# MCU.net
KiCad netlist of a schematic drawn in Altium Designer
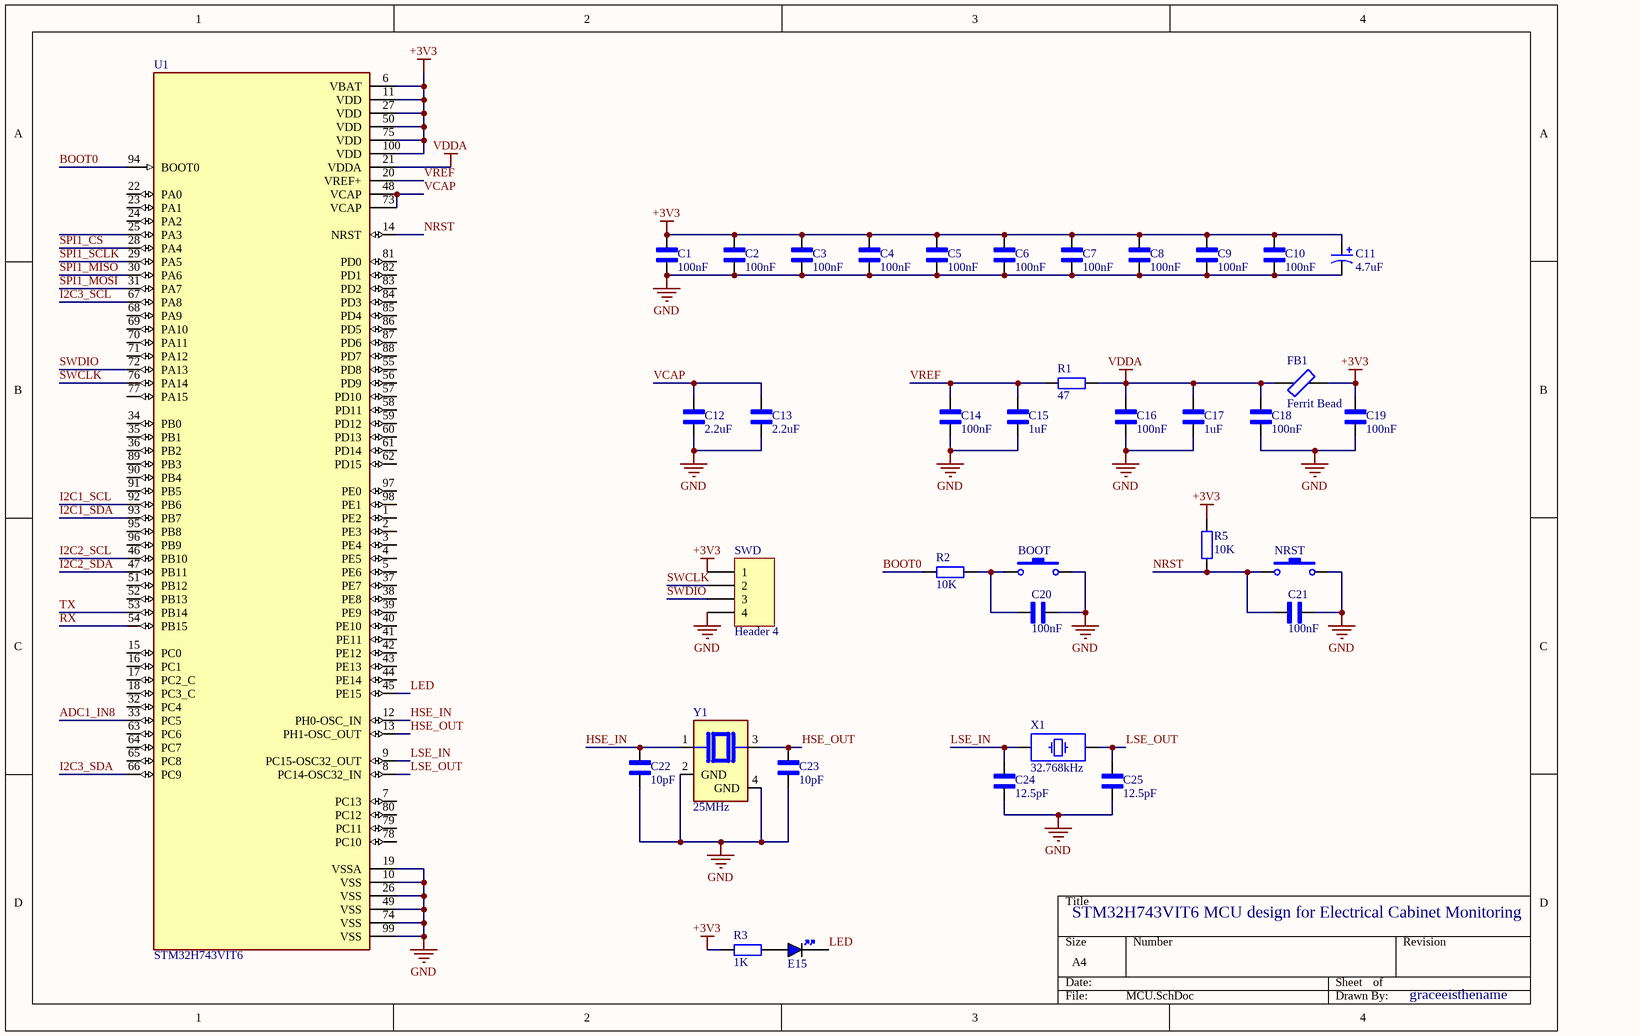
[diagram p0: MCU.SchDoc]

(export (version "E")
  (design (tool "Eeschema 10.0.6"))
  (components
    (comp (ref "BOOT")
      (value "SW-SMD")
      (footprint "SW-SMD")
      (description "Switch")
      (fields (field (name "PUBLISHER") "Altium Limited"))
      (libsource (lib "My Library") (part "SW-SMD"))
    )
    (comp (ref "C1")
      (value "100nF")
      (footprint "CAPC2012X145N")
      (description "39 pF Â±2% 200V Ceramic Capacitor C0G, NP0 0805 (2012 Metric)")
      (fields (field (name "MF") "Vishay Vitramon") (field (name "MP") "VJ0805A390GXCAP"))
      (libsource (lib "VJ0805A390GXCAP") (part "VJ0805A390GXCAP"))
    )
    (comp (ref "C2")
      (value "100nF")
      (footprint "CAPC2012X145N")
      (description "39 pF Â±2% 200V Ceramic Capacitor C0G, NP0 0805 (2012 Metric)")
      (fields (field (name "MF") "Vishay Vitramon") (field (name "MP") "VJ0805A390GXCAP"))
      (libsource (lib "VJ0805A390GXCAP") (part "VJ0805A390GXCAP"))
    )
    (comp (ref "C3")
      (value "100nF")
      (footprint "CAPC2012X145N")
      (description "39 pF Â±2% 200V Ceramic Capacitor C0G, NP0 0805 (2012 Metric)")
      (fields (field (name "MF") "Vishay Vitramon") (field (name "MP") "VJ0805A390GXCAP"))
      (libsource (lib "VJ0805A390GXCAP") (part "VJ0805A390GXCAP"))
    )
    (comp (ref "C4")
      (value "100nF")
      (footprint "CAPC2012X145N")
      (description "39 pF Â±2% 200V Ceramic Capacitor C0G, NP0 0805 (2012 Metric)")
      (fields (field (name "MF") "Vishay Vitramon") (field (name "MP") "VJ0805A390GXCAP"))
      (libsource (lib "VJ0805A390GXCAP") (part "VJ0805A390GXCAP"))
    )
    (comp (ref "C5")
      (value "100nF")
      (footprint "CAPC2012X145N")
      (description "39 pF Â±2% 200V Ceramic Capacitor C0G, NP0 0805 (2012 Metric)")
      (fields (field (name "MF") "Vishay Vitramon") (field (name "MP") "VJ0805A390GXCAP"))
      (libsource (lib "VJ0805A390GXCAP") (part "VJ0805A390GXCAP"))
    )
    (comp (ref "C6")
      (value "100nF")
      (footprint "CAPC2012X145N")
      (description "39 pF Â±2% 200V Ceramic Capacitor C0G, NP0 0805 (2012 Metric)")
      (fields (field (name "MF") "Vishay Vitramon") (field (name "MP") "VJ0805A390GXCAP"))
      (libsource (lib "VJ0805A390GXCAP") (part "VJ0805A390GXCAP"))
    )
    (comp (ref "C7")
      (value "100nF")
      (footprint "CAPC2012X145N")
      (description "39 pF Â±2% 200V Ceramic Capacitor C0G, NP0 0805 (2012 Metric)")
      (fields (field (name "MF") "Vishay Vitramon") (field (name "MP") "VJ0805A390GXCAP"))
      (libsource (lib "VJ0805A390GXCAP") (part "VJ0805A390GXCAP"))
    )
    (comp (ref "C8")
      (value "100nF")
      (footprint "CAPC2012X145N")
      (description "39 pF Â±2% 200V Ceramic Capacitor C0G, NP0 0805 (2012 Metric)")
      (fields (field (name "MF") "Vishay Vitramon") (field (name "MP") "VJ0805A390GXCAP"))
      (libsource (lib "VJ0805A390GXCAP") (part "VJ0805A390GXCAP"))
    )
    (comp (ref "C9")
      (value "100nF")
      (footprint "CAPC2012X145N")
      (description "39 pF Â±2% 200V Ceramic Capacitor C0G, NP0 0805 (2012 Metric)")
      (fields (field (name "MF") "Vishay Vitramon") (field (name "MP") "VJ0805A390GXCAP"))
      (libsource (lib "VJ0805A390GXCAP") (part "VJ0805A390GXCAP"))
    )
    (comp (ref "C10")
      (value "100nF")
      (footprint "CAPC2012X145N")
      (description "39 pF Â±2% 200V Ceramic Capacitor C0G, NP0 0805 (2012 Metric)")
      (fields (field (name "MF") "Vishay Vitramon") (field (name "MP") "VJ0805A390GXCAP"))
      (libsource (lib "VJ0805A390GXCAP") (part "VJ0805A390GXCAP"))
    )
    (comp (ref "C11")
      (value "4.7uF")
      (footprint "CAPC2012X145N")
      (description "Polazied Tantalum Capacitor")
      (libsource (lib "My Library") (part "CAP_TAN_SMD"))
    )
    (comp (ref "C12")
      (value "2.2uF")
      (footprint "CAPC2012X145N")
      (description "39 pF Â±2% 200V Ceramic Capacitor C0G, NP0 0805 (2012 Metric)")
      (fields (field (name "MF") "Vishay Vitramon") (field (name "MP") "VJ0805A390GXCAP"))
      (libsource (lib "VJ0805A390GXCAP") (part "VJ0805A390GXCAP"))
    )
    (comp (ref "C13")
      (value "2.2uF")
      (footprint "CAPC2012X145N")
      (description "39 pF Â±2% 200V Ceramic Capacitor C0G, NP0 0805 (2012 Metric)")
      (fields (field (name "MF") "Vishay Vitramon") (field (name "MP") "VJ0805A390GXCAP"))
      (libsource (lib "VJ0805A390GXCAP") (part "VJ0805A390GXCAP"))
    )
    (comp (ref "C14")
      (value "100nF")
      (footprint "CAPC2012X145N")
      (description "39 pF Â±2% 200V Ceramic Capacitor C0G, NP0 0805 (2012 Metric)")
      (fields (field (name "MF") "Vishay Vitramon") (field (name "MP") "VJ0805A390GXCAP"))
      (libsource (lib "VJ0805A390GXCAP") (part "VJ0805A390GXCAP"))
    )
    (comp (ref "C15")
      (value "1uF")
      (footprint "CAPC2012X145N")
      (description "39 pF Â±2% 200V Ceramic Capacitor C0G, NP0 0805 (2012 Metric)")
      (fields (field (name "MF") "Vishay Vitramon") (field (name "MP") "VJ0805A390GXCAP"))
      (libsource (lib "VJ0805A390GXCAP") (part "VJ0805A390GXCAP"))
    )
    (comp (ref "C16")
      (value "100nF")
      (footprint "CAPC2012X145N")
      (description "39 pF Â±2% 200V Ceramic Capacitor C0G, NP0 0805 (2012 Metric)")
      (fields (field (name "MF") "Vishay Vitramon") (field (name "MP") "VJ0805A390GXCAP"))
      (libsource (lib "VJ0805A390GXCAP") (part "VJ0805A390GXCAP"))
    )
    (comp (ref "C17")
      (value "1uF")
      (footprint "CAPC2012X145N")
      (description "39 pF Â±2% 200V Ceramic Capacitor C0G, NP0 0805 (2012 Metric)")
      (fields (field (name "MF") "Vishay Vitramon") (field (name "MP") "VJ0805A390GXCAP"))
      (libsource (lib "VJ0805A390GXCAP") (part "VJ0805A390GXCAP"))
    )
    (comp (ref "C18")
      (value "100nF")
      (footprint "CAPC2012X145N")
      (description "39 pF Â±2% 200V Ceramic Capacitor C0G, NP0 0805 (2012 Metric)")
      (fields (field (name "MF") "Vishay Vitramon") (field (name "MP") "VJ0805A390GXCAP"))
      (libsource (lib "VJ0805A390GXCAP") (part "VJ0805A390GXCAP"))
    )
    (comp (ref "C19")
      (value "100nF")
      (footprint "CAPC2012X145N")
      (description "39 pF Â±2% 200V Ceramic Capacitor C0G, NP0 0805 (2012 Metric)")
      (fields (field (name "MF") "Vishay Vitramon") (field (name "MP") "VJ0805A390GXCAP"))
      (libsource (lib "VJ0805A390GXCAP") (part "VJ0805A390GXCAP"))
    )
    (comp (ref "C20")
      (value "100nF")
      (footprint "CAPC2012X145N")
      (description "39 pF Â±2% 200V Ceramic Capacitor C0G, NP0 0805 (2012 Metric)")
      (fields (field (name "MF") "Vishay Vitramon") (field (name "MP") "VJ0805A390GXCAP"))
      (libsource (lib "") (part "VJ0805A390GXCAP_1"))
    )
    (comp (ref "C21")
      (value "100nF")
      (footprint "CAPC2012X145N")
      (description "39 pF Â±2% 200V Ceramic Capacitor C0G, NP0 0805 (2012 Metric)")
      (fields (field (name "MF") "Vishay Vitramon") (field (name "MP") "VJ0805A390GXCAP"))
      (libsource (lib "") (part "VJ0805A390GXCAP_1"))
    )
    (comp (ref "C22")
      (value "10pF")
      (footprint "CAPC2012X145N")
      (description "39 pF Â±2% 200V Ceramic Capacitor C0G, NP0 0805 (2012 Metric)")
      (fields (field (name "MF") "Vishay Vitramon") (field (name "MP") "VJ0805A390GXCAP"))
      (libsource (lib "VJ0805A390GXCAP") (part "VJ0805A390GXCAP"))
    )
    (comp (ref "C23")
      (value "10pF")
      (footprint "CAPC2012X145N")
      (description "39 pF Â±2% 200V Ceramic Capacitor C0G, NP0 0805 (2012 Metric)")
      (fields (field (name "MF") "Vishay Vitramon") (field (name "MP") "VJ0805A390GXCAP"))
      (libsource (lib "VJ0805A390GXCAP") (part "VJ0805A390GXCAP"))
    )
    (comp (ref "C24")
      (value "12.5pF")
      (footprint "CAPC2012X145N")
      (description "39 pF Â±2% 200V Ceramic Capacitor C0G, NP0 0805 (2012 Metric)")
      (fields (field (name "MF") "Vishay Vitramon") (field (name "MP") "VJ0805A390GXCAP"))
      (libsource (lib "VJ0805A390GXCAP") (part "VJ0805A390GXCAP"))
    )
    (comp (ref "C25")
      (value "12.5pF")
      (footprint "CAPC2012X145N")
      (description "39 pF Â±2% 200V Ceramic Capacitor C0G, NP0 0805 (2012 Metric)")
      (fields (field (name "MF") "Vishay Vitramon") (field (name "MP") "VJ0805A390GXCAP"))
      (libsource (lib "VJ0805A390GXCAP") (part "VJ0805A390GXCAP"))
    )
    (comp (ref "E15")
      (value "BLUE")
      (footprint "LED_0805_BLUE")
      (description "LED 0805 BLUE SMD")
      (libsource (lib "Schematic-Lib-PhilsLab") (part "LED_0805_BLUE"))
    )
    (comp (ref "FB1")
      (value "Ferrit Bead")
      (footprint "RES-SMD-0805")
      (description "Generic Ferrit Bead")
      (libsource (lib "My Library") (part "Ferrit Bead"))
    )
    (comp (ref "NRST")
      (value "SW-SMD")
      (footprint "SW-SMD")
      (description "Switch")
      (fields (field (name "PUBLISHER") "Altium Limited"))
      (libsource (lib "My Library") (part "SW-SMD"))
    )
    (comp (ref "R1")
      (value "47")
      (footprint "SM-0805")
      (description "Resistor SMD")
      (libsource (lib "My Library") (part "RM"))
    )
    (comp (ref "R2")
      (value "10K")
      (footprint "SM-0805")
      (description "Resistor SMD")
      (libsource (lib "My Library") (part "RM"))
    )
    (comp (ref "R3")
      (value "1K")
      (footprint "SM-0805")
      (description "Resistor SMD")
      (libsource (lib "My Library") (part "RM"))
    )
    (comp (ref "R5")
      (value "10K")
      (footprint "SM-0805")
      (description "Resistor SMD")
      (libsource (lib "My Library") (part "RM"))
    )
    (comp (ref "SWD")
      (value "Header 4")
      (footprint "HDR1X4")
      (description "Header, 4-Pin")
      (fields (field (name "PUBLISHER") "Altium Limited"))
      (libsource (lib "My Library") (part "Header 4"))
    )
    (comp (ref "U1")
      (value "STM32H743VIT6")
      (footprint "QFP50P1600X1600X160-100N")
      (fields (field (name "MF") "STMicroelectronics"))
      (libsource (lib "STM32H743VIT6") (part "STM32H743VIT6"))
    )
    (comp (ref "X1")
      (value "32.768kHz")
      (footprint "XTAL_3215-2")
      (description "Crystal SMD 3215")
      (libsource (lib "Schematic-Lib-PhilsLab") (part "XTAL_3215"))
    )
    (comp (ref "Y1")
      (value "25MHz")
      (footprint "XTAL_ABM8G-25.000MHZ-B4Y-T")
      (description "25 MHz Â±30ppm Crystal 10pF 60 Ohms 4-SMD, No Lead")
      (fields (field (name "MP") "ABM8G-25.000MHZ-B4Y-T") (field (name "MF") "Abracon"))
      (libsource (lib "My Library") (part "ABM8G-25.000MHZ-B4Y-T"))
    )
  )
  (nets
    (net (code "1") (name "+3V3") (class "Default")
      (node (ref "C1") (pin "2") (pinfunction "2_2") (pintype "passive"))
      (node (ref "C10") (pin "2") (pinfunction "2_2") (pintype "passive"))
      (node (ref "C11") (pin "2") (pinfunction "2_2") (pintype "passive"))
      (node (ref "C19") (pin "2") (pinfunction "2_2") (pintype "passive"))
      (node (ref "C2") (pin "2") (pinfunction "2_2") (pintype "passive"))
      (node (ref "C3") (pin "2") (pinfunction "2_2") (pintype "passive"))
      (node (ref "C4") (pin "2") (pinfunction "2_2") (pintype "passive"))
      (node (ref "C5") (pin "2") (pinfunction "2_2") (pintype "passive"))
      (node (ref "C6") (pin "2") (pinfunction "2_2") (pintype "passive"))
      (node (ref "C7") (pin "2") (pinfunction "2_2") (pintype "passive"))
      (node (ref "C8") (pin "2") (pinfunction "2_2") (pintype "passive"))
      (node (ref "C9") (pin "2") (pinfunction "2_2") (pintype "passive"))
      (node (ref "FB1") (pin "2") (pintype "passive"))
      (node (ref "R3") (pin "1") (pinfunction "1_1") (pintype "passive"))
      (node (ref "R5") (pin "2") (pinfunction "2_2") (pintype "passive"))
      (node (ref "SWD") (pin "1") (pinfunction "1_1") (pintype "passive"))
      (node (ref "U1") (pin "100") (pinfunction "VDD_100") (pintype "power_in"))
      (node (ref "U1") (pin "11") (pinfunction "VDD_11") (pintype "power_in"))
      (node (ref "U1") (pin "27") (pinfunction "VDD_27") (pintype "power_in"))
      (node (ref "U1") (pin "50") (pinfunction "VDD_50") (pintype "power_in"))
      (node (ref "U1") (pin "6") (pinfunction "VBAT_6") (pintype "power_in"))
      (node (ref "U1") (pin "75") (pinfunction "VDD_75") (pintype "power_in"))
    )
    (net (code "2") (name "/ADC1_IN8") (class "Default")
      (node (ref "U1") (pin "33") (pinfunction "PC5_33") (pintype "bidirectional"))
    )
    (net (code "3") (name "/BOOT0") (class "Default")
      (node (ref "R2") (pin "1") (pinfunction "1_1") (pintype "passive"))
      (node (ref "U1") (pin "94") (pinfunction "BOOT0_94") (pintype "input"))
    )
    (net (code "4") (name "/HSE_IN") (class "Default")
      (node (ref "C22") (pin "2") (pinfunction "2_2") (pintype "passive"))
      (node (ref "U1") (pin "12") (pinfunction "PH0-OSC_IN_12") (pintype "bidirectional"))
      (node (ref "Y1") (pin "1") (pinfunction "1_1") (pintype "passive"))
    )
    (net (code "5") (name "/HSE_OUT") (class "Default")
      (node (ref "C23") (pin "2") (pinfunction "2_2") (pintype "passive"))
      (node (ref "U1") (pin "13") (pinfunction "PH1-OSC_OUT_13") (pintype "bidirectional"))
      (node (ref "Y1") (pin "3") (pinfunction "2_3") (pintype "passive"))
    )
    (net (code "6") (name "/I2C1_SCL") (class "Default")
      (node (ref "U1") (pin "92") (pinfunction "PB6_92") (pintype "bidirectional"))
    )
    (net (code "7") (name "/I2C1_SDA") (class "Default")
      (node (ref "U1") (pin "93") (pinfunction "PB7_93") (pintype "bidirectional"))
    )
    (net (code "8") (name "/I2C2_SCL") (class "Default")
      (node (ref "U1") (pin "46") (pinfunction "PB10_46") (pintype "bidirectional"))
    )
    (net (code "9") (name "/I2C2_SDA") (class "Default")
      (node (ref "U1") (pin "47") (pinfunction "PB11_47") (pintype "bidirectional"))
    )
    (net (code "10") (name "/I2C3_SCL") (class "Default")
      (node (ref "U1") (pin "67") (pinfunction "PA8_67") (pintype "bidirectional"))
    )
    (net (code "11") (name "/I2C3_SDA") (class "Default")
      (node (ref "U1") (pin "66") (pinfunction "PC9_66") (pintype "bidirectional"))
    )
    (net (code "12") (name "/LED") (class "Default")
      (node (ref "E15") (pin "K") (pinfunction "K_K") (pintype "passive"))
      (node (ref "U1") (pin "45") (pinfunction "PE15_45") (pintype "bidirectional"))
    )
    (net (code "13") (name "/LSE_IN") (class "Default")
      (node (ref "C24") (pin "2") (pinfunction "2_2") (pintype "passive"))
      (node (ref "U1") (pin "9") (pinfunction "PC15-OSC32_OUT_9") (pintype "bidirectional"))
      (node (ref "X1") (pin "1") (pinfunction "1_1") (pintype "passive"))
    )
    (net (code "14") (name "/LSE_OUT") (class "Default")
      (node (ref "C25") (pin "2") (pinfunction "2_2") (pintype "passive"))
      (node (ref "U1") (pin "8") (pinfunction "PC14-OSC32_IN_8") (pintype "bidirectional"))
      (node (ref "X1") (pin "2") (pinfunction "2_2") (pintype "passive"))
    )
    (net (code "15") (name "/NRST") (class "Default")
      (node (ref "C21") (pin "2") (pinfunction "2_2") (pintype "passive"))
      (node (ref "NRST") (pin "1") (pinfunction "1_1") (pintype "passive"))
      (node (ref "R5") (pin "1") (pinfunction "1_1") (pintype "passive"))
      (node (ref "U1") (pin "14") (pinfunction "NRST_14") (pintype "bidirectional"))
    )
    (net (code "16") (name "/RX") (class "Default")
      (node (ref "U1") (pin "54") (pinfunction "PB15_54") (pintype "bidirectional"))
    )
    (net (code "17") (name "/SPI1_CS") (class "Default")
      (node (ref "U1") (pin "28") (pinfunction "PA4_28") (pintype "bidirectional"))
    )
    (net (code "18") (name "/SPI1_MISO") (class "Default")
      (node (ref "U1") (pin "30") (pinfunction "PA6_30") (pintype "bidirectional"))
    )
    (net (code "19") (name "/SPI1_MOSI") (class "Default")
      (node (ref "U1") (pin "31") (pinfunction "PA7_31") (pintype "bidirectional"))
    )
    (net (code "20") (name "/SPI1_SCLK") (class "Default")
      (node (ref "U1") (pin "29") (pinfunction "PA5_29") (pintype "bidirectional"))
    )
    (net (code "21") (name "/SWCLK") (class "Default")
      (node (ref "SWD") (pin "2") (pinfunction "2_2") (pintype "passive"))
      (node (ref "U1") (pin "76") (pinfunction "PA14_76") (pintype "bidirectional"))
    )
    (net (code "22") (name "/SWDIO") (class "Default")
      (node (ref "SWD") (pin "3") (pinfunction "3_3") (pintype "passive"))
      (node (ref "U1") (pin "72") (pinfunction "PA13_72") (pintype "bidirectional"))
    )
    (net (code "23") (name "/TX") (class "Default")
      (node (ref "U1") (pin "53") (pinfunction "PB14_53") (pintype "bidirectional"))
    )
    (net (code "24") (name "/VCAP") (class "Default")
      (node (ref "C12") (pin "2") (pinfunction "2_2") (pintype "passive"))
      (node (ref "C13") (pin "2") (pinfunction "2_2") (pintype "passive"))
      (node (ref "U1") (pin "48") (pinfunction "VCAP_48") (pintype "power_in"))
      (node (ref "U1") (pin "73") (pinfunction "VCAP_73") (pintype "power_in"))
    )
    (net (code "25") (name "/VREF") (class "Default")
      (node (ref "C14") (pin "2") (pinfunction "2_2") (pintype "passive"))
      (node (ref "C15") (pin "2") (pinfunction "2_2") (pintype "passive"))
      (node (ref "R1") (pin "1") (pinfunction "1_1") (pintype "passive"))
      (node (ref "U1") (pin "20") (pinfunction "VREF+_20") (pintype "power_in"))
    )
    (net (code "26") (name "GND") (class "Default")
      (node (ref "BOOT") (pin "2") (pinfunction "2_2") (pintype "passive"))
      (node (ref "C1") (pin "1") (pinfunction "1_1") (pintype "passive"))
      (node (ref "C10") (pin "1") (pinfunction "1_1") (pintype "passive"))
      (node (ref "C11") (pin "1") (pinfunction "1_1") (pintype "passive"))
      (node (ref "C12") (pin "1") (pinfunction "1_1") (pintype "passive"))
      (node (ref "C13") (pin "1") (pinfunction "1_1") (pintype "passive"))
      (node (ref "C14") (pin "1") (pinfunction "1_1") (pintype "passive"))
      (node (ref "C15") (pin "1") (pinfunction "1_1") (pintype "passive"))
      (node (ref "C16") (pin "1") (pinfunction "1_1") (pintype "passive"))
      (node (ref "C17") (pin "1") (pinfunction "1_1") (pintype "passive"))
      (node (ref "C18") (pin "1") (pinfunction "1_1") (pintype "passive"))
      (node (ref "C19") (pin "1") (pinfunction "1_1") (pintype "passive"))
      (node (ref "C2") (pin "1") (pinfunction "1_1") (pintype "passive"))
      (node (ref "C20") (pin "1") (pinfunction "1_1") (pintype "passive"))
      (node (ref "C21") (pin "1") (pinfunction "1_1") (pintype "passive"))
      (node (ref "C22") (pin "1") (pinfunction "1_1") (pintype "passive"))
      (node (ref "C23") (pin "1") (pinfunction "1_1") (pintype "passive"))
      (node (ref "C24") (pin "1") (pinfunction "1_1") (pintype "passive"))
      (node (ref "C25") (pin "1") (pinfunction "1_1") (pintype "passive"))
      (node (ref "C3") (pin "1") (pinfunction "1_1") (pintype "passive"))
      (node (ref "C4") (pin "1") (pinfunction "1_1") (pintype "passive"))
      (node (ref "C5") (pin "1") (pinfunction "1_1") (pintype "passive"))
      (node (ref "C6") (pin "1") (pinfunction "1_1") (pintype "passive"))
      (node (ref "C7") (pin "1") (pinfunction "1_1") (pintype "passive"))
      (node (ref "C8") (pin "1") (pinfunction "1_1") (pintype "passive"))
      (node (ref "C9") (pin "1") (pinfunction "1_1") (pintype "passive"))
      (node (ref "NRST") (pin "2") (pinfunction "2_2") (pintype "passive"))
      (node (ref "SWD") (pin "4") (pinfunction "4_4") (pintype "passive"))
      (node (ref "U1") (pin "10") (pinfunction "VSS_10") (pintype "power_in"))
      (node (ref "U1") (pin "19") (pinfunction "VSSA_19") (pintype "power_in"))
      (node (ref "U1") (pin "26") (pinfunction "VSS_26") (pintype "power_in"))
      (node (ref "U1") (pin "49") (pinfunction "VSS_49") (pintype "power_in"))
      (node (ref "U1") (pin "74") (pinfunction "VSS_74") (pintype "power_in"))
      (node (ref "U1") (pin "99") (pinfunction "VSS_99") (pintype "power_in"))
      (node (ref "Y1") (pin "2") (pinfunction "GND_2") (pintype "power_in"))
      (node (ref "Y1") (pin "4") (pinfunction "GND_4") (pintype "power_in"))
    )
    (net (code "27") (name "Net-(BOOT-Pad1)") (class "Default")
      (node (ref "BOOT") (pin "1") (pinfunction "1_1") (pintype "passive"))
      (node (ref "C20") (pin "2") (pinfunction "2_2") (pintype "passive"))
      (node (ref "R2") (pin "2") (pinfunction "2_2") (pintype "passive"))
    )
    (net (code "28") (name "Net-(E15-PadA)") (class "Default")
      (node (ref "E15") (pin "A") (pinfunction "A_A") (pintype "passive"))
      (node (ref "R3") (pin "2") (pinfunction "2_2") (pintype "passive"))
    )
    (net (code "29") (name "VDDA") (class "Default")
      (node (ref "C16") (pin "2") (pinfunction "2_2") (pintype "passive"))
      (node (ref "C17") (pin "2") (pinfunction "2_2") (pintype "passive"))
      (node (ref "C18") (pin "2") (pinfunction "2_2") (pintype "passive"))
      (node (ref "FB1") (pin "1") (pintype "passive"))
      (node (ref "R1") (pin "2") (pinfunction "2_2") (pintype "passive"))
      (node (ref "U1") (pin "21") (pinfunction "VDDA_21") (pintype "power_in"))
    )
    (net (code "30") (name "unconnected-(U1-PA0-Pad22)") (class "Default")
      (node (ref "U1") (pin "22") (pinfunction "PA0_22") (pintype "bidirectional"))
    )
    (net (code "31") (name "unconnected-(U1-PA1-Pad23)") (class "Default")
      (node (ref "U1") (pin "23") (pinfunction "PA1_23") (pintype "bidirectional"))
    )
    (net (code "32") (name "unconnected-(U1-PA2-Pad24)") (class "Default")
      (node (ref "U1") (pin "24") (pinfunction "PA2_24") (pintype "bidirectional"))
    )
    (net (code "33") (name "unconnected-(U1-PA3-Pad25)") (class "Default")
      (node (ref "U1") (pin "25") (pinfunction "PA3_25") (pintype "bidirectional"))
    )
    (net (code "34") (name "unconnected-(U1-PA9-Pad68)") (class "Default")
      (node (ref "U1") (pin "68") (pinfunction "PA9_68") (pintype "bidirectional"))
    )
    (net (code "35") (name "unconnected-(U1-PA10-Pad69)") (class "Default")
      (node (ref "U1") (pin "69") (pinfunction "PA10_69") (pintype "bidirectional"))
    )
    (net (code "36") (name "unconnected-(U1-PA11-Pad70)") (class "Default")
      (node (ref "U1") (pin "70") (pinfunction "PA11_70") (pintype "bidirectional"))
    )
    (net (code "37") (name "unconnected-(U1-PA12-Pad71)") (class "Default")
      (node (ref "U1") (pin "71") (pinfunction "PA12_71") (pintype "bidirectional"))
    )
    (net (code "38") (name "unconnected-(U1-PA15-Pad77)") (class "Default")
      (node (ref "U1") (pin "77") (pinfunction "PA15_77") (pintype "bidirectional"))
    )
    (net (code "39") (name "unconnected-(U1-PB0-Pad34)") (class "Default")
      (node (ref "U1") (pin "34") (pinfunction "PB0_34") (pintype "bidirectional"))
    )
    (net (code "40") (name "unconnected-(U1-PB1-Pad35)") (class "Default")
      (node (ref "U1") (pin "35") (pinfunction "PB1_35") (pintype "bidirectional"))
    )
    (net (code "41") (name "unconnected-(U1-PB2-Pad36)") (class "Default")
      (node (ref "U1") (pin "36") (pinfunction "PB2_36") (pintype "bidirectional"))
    )
    (net (code "42") (name "unconnected-(U1-PB3-Pad89)") (class "Default")
      (node (ref "U1") (pin "89") (pinfunction "PB3_89") (pintype "bidirectional"))
    )
    (net (code "43") (name "unconnected-(U1-PB4-Pad90)") (class "Default")
      (node (ref "U1") (pin "90") (pinfunction "PB4_90") (pintype "bidirectional"))
    )
    (net (code "44") (name "unconnected-(U1-PB5-Pad91)") (class "Default")
      (node (ref "U1") (pin "91") (pinfunction "PB5_91") (pintype "bidirectional"))
    )
    (net (code "45") (name "unconnected-(U1-PB8-Pad95)") (class "Default")
      (node (ref "U1") (pin "95") (pinfunction "PB8_95") (pintype "bidirectional"))
    )
    (net (code "46") (name "unconnected-(U1-PB9-Pad96)") (class "Default")
      (node (ref "U1") (pin "96") (pinfunction "PB9_96") (pintype "bidirectional"))
    )
    (net (code "47") (name "unconnected-(U1-PB12-Pad51)") (class "Default")
      (node (ref "U1") (pin "51") (pinfunction "PB12_51") (pintype "bidirectional"))
    )
    (net (code "48") (name "unconnected-(U1-PB13-Pad52)") (class "Default")
      (node (ref "U1") (pin "52") (pinfunction "PB13_52") (pintype "bidirectional"))
    )
    (net (code "49") (name "unconnected-(U1-PC0-Pad15)") (class "Default")
      (node (ref "U1") (pin "15") (pinfunction "PC0_15") (pintype "bidirectional"))
    )
    (net (code "50") (name "unconnected-(U1-PC1-Pad16)") (class "Default")
      (node (ref "U1") (pin "16") (pinfunction "PC1_16") (pintype "bidirectional"))
    )
    (net (code "51") (name "unconnected-(U1-PC2_C-Pad17)") (class "Default")
      (node (ref "U1") (pin "17") (pinfunction "PC2_C_17") (pintype "bidirectional"))
    )
    (net (code "52") (name "unconnected-(U1-PC3_C-Pad18)") (class "Default")
      (node (ref "U1") (pin "18") (pinfunction "PC3_C_18") (pintype "bidirectional"))
    )
    (net (code "53") (name "unconnected-(U1-PC4-Pad32)") (class "Default")
      (node (ref "U1") (pin "32") (pinfunction "PC4_32") (pintype "bidirectional"))
    )
    (net (code "54") (name "unconnected-(U1-PC6-Pad63)") (class "Default")
      (node (ref "U1") (pin "63") (pinfunction "PC6_63") (pintype "bidirectional"))
    )
    (net (code "55") (name "unconnected-(U1-PC7-Pad64)") (class "Default")
      (node (ref "U1") (pin "64") (pinfunction "PC7_64") (pintype "bidirectional"))
    )
    (net (code "56") (name "unconnected-(U1-PC8-Pad65)") (class "Default")
      (node (ref "U1") (pin "65") (pinfunction "PC8_65") (pintype "bidirectional"))
    )
    (net (code "57") (name "unconnected-(U1-PC10-Pad78)") (class "Default")
      (node (ref "U1") (pin "78") (pinfunction "PC10_78") (pintype "bidirectional"))
    )
    (net (code "58") (name "unconnected-(U1-PC11-Pad79)") (class "Default")
      (node (ref "U1") (pin "79") (pinfunction "PC11_79") (pintype "bidirectional"))
    )
    (net (code "59") (name "unconnected-(U1-PC12-Pad80)") (class "Default")
      (node (ref "U1") (pin "80") (pinfunction "PC12_80") (pintype "bidirectional"))
    )
    (net (code "60") (name "unconnected-(U1-PC13-Pad7)") (class "Default")
      (node (ref "U1") (pin "7") (pinfunction "PC13_7") (pintype "bidirectional"))
    )
    (net (code "61") (name "unconnected-(U1-PD0-Pad81)") (class "Default")
      (node (ref "U1") (pin "81") (pinfunction "PD0_81") (pintype "bidirectional"))
    )
    (net (code "62") (name "unconnected-(U1-PD1-Pad82)") (class "Default")
      (node (ref "U1") (pin "82") (pinfunction "PD1_82") (pintype "bidirectional"))
    )
    (net (code "63") (name "unconnected-(U1-PD2-Pad83)") (class "Default")
      (node (ref "U1") (pin "83") (pinfunction "PD2_83") (pintype "bidirectional"))
    )
    (net (code "64") (name "unconnected-(U1-PD3-Pad84)") (class "Default")
      (node (ref "U1") (pin "84") (pinfunction "PD3_84") (pintype "bidirectional"))
    )
    (net (code "65") (name "unconnected-(U1-PD4-Pad85)") (class "Default")
      (node (ref "U1") (pin "85") (pinfunction "PD4_85") (pintype "bidirectional"))
    )
    (net (code "66") (name "unconnected-(U1-PD5-Pad86)") (class "Default")
      (node (ref "U1") (pin "86") (pinfunction "PD5_86") (pintype "bidirectional"))
    )
    (net (code "67") (name "unconnected-(U1-PD6-Pad87)") (class "Default")
      (node (ref "U1") (pin "87") (pinfunction "PD6_87") (pintype "bidirectional"))
    )
    (net (code "68") (name "unconnected-(U1-PD7-Pad88)") (class "Default")
      (node (ref "U1") (pin "88") (pinfunction "PD7_88") (pintype "bidirectional"))
    )
    (net (code "69") (name "unconnected-(U1-PD8-Pad55)") (class "Default")
      (node (ref "U1") (pin "55") (pinfunction "PD8_55") (pintype "bidirectional"))
    )
    (net (code "70") (name "unconnected-(U1-PD9-Pad56)") (class "Default")
      (node (ref "U1") (pin "56") (pinfunction "PD9_56") (pintype "bidirectional"))
    )
    (net (code "71") (name "unconnected-(U1-PD10-Pad57)") (class "Default")
      (node (ref "U1") (pin "57") (pinfunction "PD10_57") (pintype "bidirectional"))
    )
    (net (code "72") (name "unconnected-(U1-PD11-Pad58)") (class "Default")
      (node (ref "U1") (pin "58") (pinfunction "PD11_58") (pintype "bidirectional"))
    )
    (net (code "73") (name "unconnected-(U1-PD12-Pad59)") (class "Default")
      (node (ref "U1") (pin "59") (pinfunction "PD12_59") (pintype "bidirectional"))
    )
    (net (code "74") (name "unconnected-(U1-PD13-Pad60)") (class "Default")
      (node (ref "U1") (pin "60") (pinfunction "PD13_60") (pintype "bidirectional"))
    )
    (net (code "75") (name "unconnected-(U1-PD14-Pad61)") (class "Default")
      (node (ref "U1") (pin "61") (pinfunction "PD14_61") (pintype "bidirectional"))
    )
    (net (code "76") (name "unconnected-(U1-PD15-Pad62)") (class "Default")
      (node (ref "U1") (pin "62") (pinfunction "PD15_62") (pintype "bidirectional"))
    )
    (net (code "77") (name "unconnected-(U1-PE0-Pad97)") (class "Default")
      (node (ref "U1") (pin "97") (pinfunction "PE0_97") (pintype "bidirectional"))
    )
    (net (code "78") (name "unconnected-(U1-PE1-Pad98)") (class "Default")
      (node (ref "U1") (pin "98") (pinfunction "PE1_98") (pintype "bidirectional"))
    )
    (net (code "79") (name "unconnected-(U1-PE2-Pad1)") (class "Default")
      (node (ref "U1") (pin "1") (pinfunction "PE2_1") (pintype "bidirectional"))
    )
    (net (code "80") (name "unconnected-(U1-PE3-Pad2)") (class "Default")
      (node (ref "U1") (pin "2") (pinfunction "PE3_2") (pintype "bidirectional"))
    )
    (net (code "81") (name "unconnected-(U1-PE4-Pad3)") (class "Default")
      (node (ref "U1") (pin "3") (pinfunction "PE4_3") (pintype "bidirectional"))
    )
    (net (code "82") (name "unconnected-(U1-PE5-Pad4)") (class "Default")
      (node (ref "U1") (pin "4") (pinfunction "PE5_4") (pintype "bidirectional"))
    )
    (net (code "83") (name "unconnected-(U1-PE6-Pad5)") (class "Default")
      (node (ref "U1") (pin "5") (pinfunction "PE6_5") (pintype "bidirectional"))
    )
    (net (code "84") (name "unconnected-(U1-PE7-Pad37)") (class "Default")
      (node (ref "U1") (pin "37") (pinfunction "PE7_37") (pintype "bidirectional"))
    )
    (net (code "85") (name "unconnected-(U1-PE8-Pad38)") (class "Default")
      (node (ref "U1") (pin "38") (pinfunction "PE8_38") (pintype "bidirectional"))
    )
    (net (code "86") (name "unconnected-(U1-PE9-Pad39)") (class "Default")
      (node (ref "U1") (pin "39") (pinfunction "PE9_39") (pintype "bidirectional"))
    )
    (net (code "87") (name "unconnected-(U1-PE10-Pad40)") (class "Default")
      (node (ref "U1") (pin "40") (pinfunction "PE10_40") (pintype "bidirectional"))
    )
    (net (code "88") (name "unconnected-(U1-PE11-Pad41)") (class "Default")
      (node (ref "U1") (pin "41") (pinfunction "PE11_41") (pintype "bidirectional"))
    )
    (net (code "89") (name "unconnected-(U1-PE12-Pad42)") (class "Default")
      (node (ref "U1") (pin "42") (pinfunction "PE12_42") (pintype "bidirectional"))
    )
    (net (code "90") (name "unconnected-(U1-PE13-Pad43)") (class "Default")
      (node (ref "U1") (pin "43") (pinfunction "PE13_43") (pintype "bidirectional"))
    )
    (net (code "91") (name "unconnected-(U1-PE14-Pad44)") (class "Default")
      (node (ref "U1") (pin "44") (pinfunction "PE14_44") (pintype "bidirectional"))
    )
  )
)
